# makey_makey.net
KiCad netlist of a schematic drawn in EAGLE
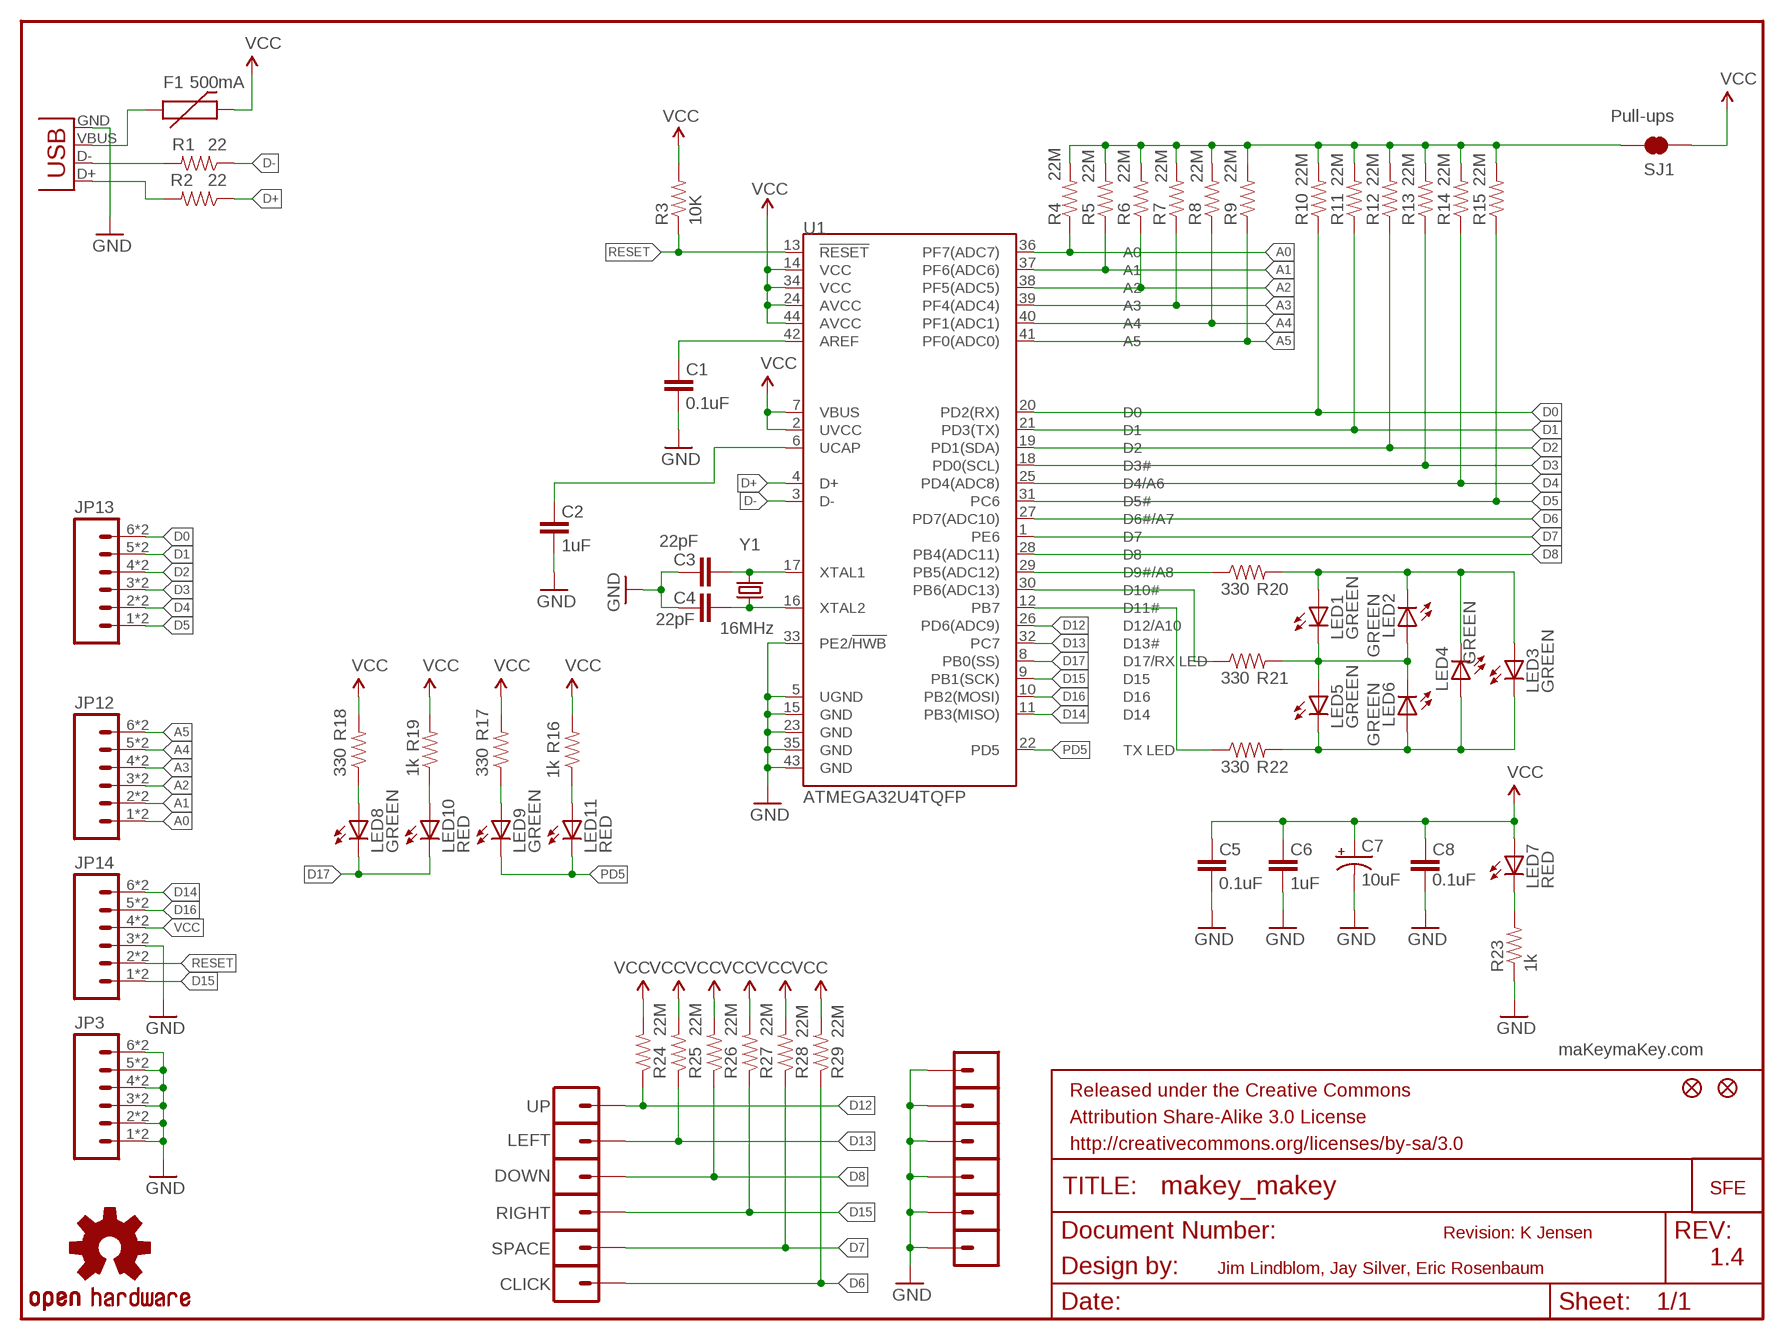
[diagram p0: schematic, sheet 1]

(export (version "E")
  (design (tool "Eeschema 10.0.6"))
  (components
    (comp (ref "C1")
      (value "0.1uF")
      (footprint "eagle-import:0603-CAP")
      (libsource (lib "eagle-import") (part "CAP0603-CAP"))
    )
    (comp (ref "C2")
      (value "1uF")
      (footprint "eagle-import:0603-CAP")
      (libsource (lib "eagle-import") (part "CAP0603-CAP"))
    )
    (comp (ref "C3")
      (value "22pF")
      (footprint "eagle-import:0603-CAP")
      (libsource (lib "eagle-import") (part "CAP0603-CAP"))
    )
    (comp (ref "C4")
      (value "22pF")
      (footprint "eagle-import:0603-CAP")
      (libsource (lib "eagle-import") (part "CAP0603-CAP"))
    )
    (comp (ref "C5")
      (value "0.1uF")
      (footprint "eagle-import:0603-CAP")
      (libsource (lib "eagle-import") (part "CAP0603-CAP"))
    )
    (comp (ref "C6")
      (value "1uF")
      (footprint "eagle-import:0603-CAP")
      (libsource (lib "eagle-import") (part "CAP0603-CAP"))
    )
    (comp (ref "C7")
      (value "10uF")
      (footprint "eagle-import:EIA3216")
      (libsource (lib "eagle-import") (part "CAP_POL1206"))
    )
    (comp (ref "C8")
      (value "0.1uF")
      (footprint "eagle-import:0603-CAP")
      (libsource (lib "eagle-import") (part "CAP0603-CAP"))
    )
    (comp (ref "CLICK")
      (value "M01ALLIGATOR-3MM")
      (footprint "eagle-import:1X01_ALLIGATOR_3MM")
      (libsource (lib "eagle-import") (part "M01ALLIGATOR-3MM"))
    )
    (comp (ref "DOWN")
      (value "M01ALLIGATOR-3MM")
      (footprint "eagle-import:1X01_ALLIGATOR_3MM")
      (libsource (lib "eagle-import") (part "M01ALLIGATOR-3MM"))
    )
    (comp (ref "F1")
      (value "500mA")
      (footprint "eagle-import:PTC-1206-WIDE")
      (libsource (lib "eagle-import") (part "PTCSMD-W"))
    )
    (comp (ref "JP1")
      (value "FIDUCIALUFIDUCIAL")
      (footprint "eagle-import:MICRO-FIDUCIAL")
      (libsource (lib "eagle-import") (part "FIDUCIALUFIDUCIAL"))
    )
    (comp (ref "JP2")
      (value "FIDUCIALUFIDUCIAL")
      (footprint "eagle-import:MICRO-FIDUCIAL")
      (libsource (lib "eagle-import") (part "FIDUCIALUFIDUCIAL"))
    )
    (comp (ref "JP3")
      (value "M06SMD-STRAIGHT-COMBO")
      (footprint "eagle-import:1X06_SMD_STRAIGHT_COMBO")
      (libsource (lib "eagle-import") (part "M06SMD-STRAIGHT-COMBO"))
    )
    (comp (ref "JP5")
      (value "M01ALLIGATOR-3MM")
      (footprint "eagle-import:1X01_ALLIGATOR_3MM")
      (libsource (lib "eagle-import") (part "M01ALLIGATOR-3MM"))
    )
    (comp (ref "JP6")
      (value "M01ALLIGATOR-3MM")
      (footprint "eagle-import:1X01_ALLIGATOR_3MM")
      (libsource (lib "eagle-import") (part "M01ALLIGATOR-3MM"))
    )
    (comp (ref "JP7")
      (value "M01ALLIGATOR-3MM")
      (footprint "eagle-import:1X01_ALLIGATOR_3MM")
      (libsource (lib "eagle-import") (part "M01ALLIGATOR-3MM"))
    )
    (comp (ref "JP8")
      (value "M01ALLIGATOR-3MM")
      (footprint "eagle-import:1X01_ALLIGATOR_3MM")
      (libsource (lib "eagle-import") (part "M01ALLIGATOR-3MM"))
    )
    (comp (ref "JP9")
      (value "LOGO-SFENEW")
      (footprint "eagle-import:SFE-NEW-WEBLOGO")
      (libsource (lib "eagle-import") (part "LOGO-SFENEW"))
    )
    (comp (ref "JP10")
      (value "M01ALLIGATOR-3MM")
      (footprint "eagle-import:1X01_ALLIGATOR_3MM")
      (libsource (lib "eagle-import") (part "M01ALLIGATOR-3MM"))
    )
    (comp (ref "JP11")
      (value "M01ALLIGATOR-3MM")
      (footprint "eagle-import:1X01_ALLIGATOR_3MM")
      (libsource (lib "eagle-import") (part "M01ALLIGATOR-3MM"))
    )
    (comp (ref "JP12")
      (value "M06SMD-STRAIGHT-COMBO")
      (footprint "eagle-import:1X06_SMD_STRAIGHT_COMBO")
      (libsource (lib "eagle-import") (part "M06SMD-STRAIGHT-COMBO"))
    )
    (comp (ref "JP13")
      (value "M06SMD-STRAIGHT-COMBO")
      (footprint "eagle-import:1X06_SMD_STRAIGHT_COMBO")
      (libsource (lib "eagle-import") (part "M06SMD-STRAIGHT-COMBO"))
    )
    (comp (ref "JP14")
      (value "M06SMD-STRAIGHT-COMBO")
      (footprint "eagle-import:1X06_SMD_STRAIGHT_COMBO")
      (libsource (lib "eagle-import") (part "M06SMD-STRAIGHT-COMBO"))
    )
    (comp (ref "LED1")
      (value "GREEN")
      (footprint "eagle-import:LED-1206-BOTTOM")
      (libsource (lib "eagle-import") (part "LED1206-BOTTOM"))
    )
    (comp (ref "LED2")
      (value "GREEN")
      (footprint "eagle-import:LED-1206-BOTTOM")
      (libsource (lib "eagle-import") (part "LED1206-BOTTOM"))
    )
    (comp (ref "LED3")
      (value "GREEN")
      (footprint "eagle-import:LED-1206-BOTTOM")
      (libsource (lib "eagle-import") (part "LED1206-BOTTOM"))
    )
    (comp (ref "LED4")
      (value "GREEN")
      (footprint "eagle-import:LED-1206-BOTTOM")
      (libsource (lib "eagle-import") (part "LED1206-BOTTOM"))
    )
    (comp (ref "LED5")
      (value "GREEN")
      (footprint "eagle-import:LED-1206-BOTTOM")
      (libsource (lib "eagle-import") (part "LED1206-BOTTOM"))
    )
    (comp (ref "LED6")
      (value "GREEN")
      (footprint "eagle-import:LED-1206-BOTTOM")
      (libsource (lib "eagle-import") (part "LED1206-BOTTOM"))
    )
    (comp (ref "LED7")
      (value "RED")
      (footprint "eagle-import:LED-0603")
      (libsource (lib "eagle-import") (part "LED0603"))
    )
    (comp (ref "LED8")
      (value "GREEN")
      (footprint "eagle-import:LED-0603")
      (libsource (lib "eagle-import") (part "SparkFun-LED_LED0603"))
    )
    (comp (ref "LED9")
      (value "GREEN")
      (footprint "eagle-import:LED-0603")
      (libsource (lib "eagle-import") (part "SparkFun-LED_LED0603"))
    )
    (comp (ref "LED10")
      (value "RED")
      (footprint "eagle-import:LED-0603")
      (libsource (lib "eagle-import") (part "SparkFun-LED_LED0603"))
    )
    (comp (ref "LED11")
      (value "RED")
      (footprint "eagle-import:LED-0603")
      (libsource (lib "eagle-import") (part "SparkFun-LED_LED0603"))
    )
    (comp (ref "LEFT")
      (value "M01ALLIGATOR-3MM")
      (footprint "eagle-import:1X01_ALLIGATOR_3MM")
      (libsource (lib "eagle-import") (part "M01ALLIGATOR-3MM"))
    )
    (comp (ref "R1")
      (value "22")
      (footprint "eagle-import:0603-RES")
      (libsource (lib "eagle-import") (part "RESISTOR0603-RES"))
    )
    (comp (ref "R2")
      (value "22")
      (footprint "eagle-import:0603-RES")
      (libsource (lib "eagle-import") (part "RESISTOR0603-RES"))
    )
    (comp (ref "R3")
      (value "10K")
      (footprint "eagle-import:0603-RES")
      (libsource (lib "eagle-import") (part "RESISTOR0603-RES"))
    )
    (comp (ref "R4")
      (value "22M")
      (footprint "eagle-import:0603-RES")
      (libsource (lib "eagle-import") (part "RESISTOR0603-RES"))
    )
    (comp (ref "R5")
      (value "22M")
      (footprint "eagle-import:0603-RES")
      (libsource (lib "eagle-import") (part "RESISTOR0603-RES"))
    )
    (comp (ref "R6")
      (value "22M")
      (footprint "eagle-import:0603-RES")
      (libsource (lib "eagle-import") (part "RESISTOR0603-RES"))
    )
    (comp (ref "R7")
      (value "22M")
      (footprint "eagle-import:0603-RES")
      (libsource (lib "eagle-import") (part "RESISTOR0603-RES"))
    )
    (comp (ref "R8")
      (value "22M")
      (footprint "eagle-import:0603-RES")
      (libsource (lib "eagle-import") (part "RESISTOR0603-RES"))
    )
    (comp (ref "R9")
      (value "22M")
      (footprint "eagle-import:0603-RES")
      (libsource (lib "eagle-import") (part "RESISTOR0603-RES"))
    )
    (comp (ref "R10")
      (value "22M")
      (footprint "eagle-import:0603-RES")
      (libsource (lib "eagle-import") (part "RESISTOR0603-RES"))
    )
    (comp (ref "R11")
      (value "22M")
      (footprint "eagle-import:0603-RES")
      (libsource (lib "eagle-import") (part "RESISTOR0603-RES"))
    )
    (comp (ref "R12")
      (value "22M")
      (footprint "eagle-import:0603-RES")
      (libsource (lib "eagle-import") (part "RESISTOR0603-RES"))
    )
    (comp (ref "R13")
      (value "22M")
      (footprint "eagle-import:0603-RES")
      (libsource (lib "eagle-import") (part "RESISTOR0603-RES"))
    )
    (comp (ref "R14")
      (value "22M")
      (footprint "eagle-import:0603-RES")
      (libsource (lib "eagle-import") (part "RESISTOR0603-RES"))
    )
    (comp (ref "R15")
      (value "22M")
      (footprint "eagle-import:0603-RES")
      (libsource (lib "eagle-import") (part "RESISTOR0603-RES"))
    )
    (comp (ref "R16")
      (value "1k")
      (footprint "eagle-import:0603-RES")
      (libsource (lib "eagle-import") (part "SparkFun-Passives_RESISTOR0603-RES"))
    )
    (comp (ref "R17")
      (value "330")
      (footprint "eagle-import:0603-RES")
      (libsource (lib "eagle-import") (part "SparkFun-Passives_RESISTOR0603-RES"))
    )
    (comp (ref "R18")
      (value "330")
      (footprint "eagle-import:0603-RES")
      (libsource (lib "eagle-import") (part "SparkFun-Passives_RESISTOR0603-RES"))
    )
    (comp (ref "R19")
      (value "1k")
      (footprint "eagle-import:0603-RES")
      (libsource (lib "eagle-import") (part "SparkFun-Passives_RESISTOR0603-RES"))
    )
    (comp (ref "R20")
      (value "330")
      (footprint "eagle-import:0603-RES")
      (libsource (lib "eagle-import") (part "SparkFun-Passives_RESISTOR0603-RES"))
    )
    (comp (ref "R21")
      (value "330")
      (footprint "eagle-import:0603-RES")
      (libsource (lib "eagle-import") (part "SparkFun-Passives_RESISTOR0603-RES"))
    )
    (comp (ref "R22")
      (value "330")
      (footprint "eagle-import:0603-RES")
      (libsource (lib "eagle-import") (part "SparkFun-Passives_RESISTOR0603-RES"))
    )
    (comp (ref "R23")
      (value "1k")
      (footprint "eagle-import:0603-RES")
      (libsource (lib "eagle-import") (part "RESISTOR0603-RES"))
    )
    (comp (ref "R24")
      (value "22M")
      (footprint "eagle-import:0603-RES")
      (libsource (lib "eagle-import") (part "RESISTOR0603-RES"))
    )
    (comp (ref "R25")
      (value "22M")
      (footprint "eagle-import:0603-RES")
      (libsource (lib "eagle-import") (part "RESISTOR0603-RES"))
    )
    (comp (ref "R26")
      (value "22M")
      (footprint "eagle-import:0603-RES")
      (libsource (lib "eagle-import") (part "RESISTOR0603-RES"))
    )
    (comp (ref "R27")
      (value "22M")
      (footprint "eagle-import:0603-RES")
      (libsource (lib "eagle-import") (part "RESISTOR0603-RES"))
    )
    (comp (ref "R28")
      (value "22M")
      (footprint "eagle-import:0603-RES")
      (libsource (lib "eagle-import") (part "RESISTOR0603-RES"))
    )
    (comp (ref "R29")
      (value "22M")
      (footprint "eagle-import:0603-RES")
      (libsource (lib "eagle-import") (part "RESISTOR0603-RES"))
    )
    (comp (ref "RIGHT")
      (value "M01ALLIGATOR-3MM")
      (footprint "eagle-import:1X01_ALLIGATOR_3MM")
      (libsource (lib "eagle-import") (part "M01ALLIGATOR-3MM"))
    )
    (comp (ref "SJ1")
      (value "Pull-ups")
      (footprint "eagle-import:SJ_2S-TRACE")
      (libsource (lib "eagle-import") (part "SOLDERJUMPER-OLDTRACE"))
    )
    (comp (ref "SPACE")
      (value "M01ALLIGATOR-3MM")
      (footprint "eagle-import:1X01_ALLIGATOR_3MM")
      (libsource (lib "eagle-import") (part "M01ALLIGATOR-3MM"))
    )
    (comp (ref "U$1")
      (value "OSHW-LOGOM")
      (footprint "eagle-import:OSHW-LOGO-M")
      (libsource (lib "eagle-import") (part "OSHW-LOGOM"))
    )
    (comp (ref "U1")
      (value "ATMEGA32U4TQFP")
      (footprint "eagle-import:TQFP44")
      (libsource (lib "eagle-import") (part "ATMEGA32U4TQFP"))
    )
    (comp (ref "UP")
      (value "M01ALLIGATOR-3MM")
      (footprint "eagle-import:1X01_ALLIGATOR_3MM")
      (libsource (lib "eagle-import") (part "M01ALLIGATOR-3MM"))
    )
    (comp (ref "X1")
      (value "USBSMD")
      (footprint "eagle-import:USB-MINIB")
      (libsource (lib "eagle-import") (part "USBSMD"))
    )
    (comp (ref "Y1")
      (value "16MHz")
      (footprint "eagle-import:CRYSTAL-SMD-5X3")
      (libsource (lib "eagle-import") (part "CRYSTAL5X3"))
    )
  )
  (nets
    (net (code "1") (name "A0") (class "Default")
      (node (ref "JP12") (pin "1") (pinfunction "1_1") (pintype "passive"))
      (node (ref "JP12") (pin "1-2") (pinfunction "1_1-2") (pintype "passive"))
      (node (ref "R4") (pin "1") (pinfunction "1_1") (pintype "passive"))
      (node (ref "U1") (pin "36") (pinfunction "PF7(ADC7)_36") (pintype "bidirectional"))
    )
    (net (code "2") (name "A1") (class "Default")
      (node (ref "JP12") (pin "2") (pinfunction "2_2") (pintype "passive"))
      (node (ref "JP12") (pin "2-2") (pinfunction "2_2-2") (pintype "passive"))
      (node (ref "R5") (pin "1") (pinfunction "1_1") (pintype "passive"))
      (node (ref "U1") (pin "37") (pinfunction "PF6(ADC6)_37") (pintype "bidirectional"))
    )
    (net (code "3") (name "A2") (class "Default")
      (node (ref "JP12") (pin "3") (pinfunction "3_3") (pintype "passive"))
      (node (ref "JP12") (pin "3-2") (pinfunction "3_3-2") (pintype "passive"))
      (node (ref "R6") (pin "1") (pinfunction "1_1") (pintype "passive"))
      (node (ref "U1") (pin "38") (pinfunction "PF5(ADC5)_38") (pintype "bidirectional"))
    )
    (net (code "4") (name "A3") (class "Default")
      (node (ref "JP12") (pin "4") (pinfunction "4_4") (pintype "passive"))
      (node (ref "JP12") (pin "4-2") (pinfunction "4_4-2") (pintype "passive"))
      (node (ref "R7") (pin "1") (pinfunction "1_1") (pintype "passive"))
      (node (ref "U1") (pin "39") (pinfunction "PF4(ADC4)_39") (pintype "bidirectional"))
    )
    (net (code "5") (name "A4") (class "Default")
      (node (ref "JP12") (pin "5") (pinfunction "5_5") (pintype "passive"))
      (node (ref "JP12") (pin "5-2") (pinfunction "5_5-2") (pintype "passive"))
      (node (ref "R8") (pin "1") (pinfunction "1_1") (pintype "passive"))
      (node (ref "U1") (pin "40") (pinfunction "PF1(ADC1)_40") (pintype "bidirectional"))
    )
    (net (code "6") (name "A5") (class "Default")
      (node (ref "JP12") (pin "6") (pinfunction "6_6") (pintype "passive"))
      (node (ref "JP12") (pin "6-2") (pinfunction "6_6-2") (pintype "passive"))
      (node (ref "R9") (pin "1") (pinfunction "1_1") (pintype "passive"))
      (node (ref "U1") (pin "41") (pinfunction "PF0(ADC0)_41") (pintype "bidirectional"))
    )
    (net (code "7") (name "D+") (class "Default")
      (node (ref "R2") (pin "1") (pinfunction "1_1") (pintype "passive"))
      (node (ref "U1") (pin "4") (pinfunction "D+_4") (pintype "bidirectional"))
    )
    (net (code "8") (name "D-") (class "Default")
      (node (ref "R1") (pin "1") (pinfunction "1_1") (pintype "passive"))
      (node (ref "U1") (pin "3") (pinfunction "D-_3") (pintype "bidirectional"))
    )
    (net (code "9") (name "D0") (class "Default")
      (node (ref "JP13") (pin "6") (pinfunction "6_6") (pintype "passive"))
      (node (ref "JP13") (pin "6-2") (pinfunction "6_6-2") (pintype "passive"))
      (node (ref "R10") (pin "1") (pinfunction "1_1") (pintype "passive"))
      (node (ref "U1") (pin "20") (pinfunction "PD2(RX)_20") (pintype "bidirectional"))
    )
    (net (code "10") (name "D1") (class "Default")
      (node (ref "JP13") (pin "5") (pinfunction "5_5") (pintype "passive"))
      (node (ref "JP13") (pin "5-2") (pinfunction "5_5-2") (pintype "passive"))
      (node (ref "R11") (pin "1") (pinfunction "1_1") (pintype "passive"))
      (node (ref "U1") (pin "21") (pinfunction "PD3(TX)_21") (pintype "bidirectional"))
    )
    (net (code "11") (name "D2") (class "Default")
      (node (ref "JP13") (pin "4") (pinfunction "4_4") (pintype "passive"))
      (node (ref "JP13") (pin "4-2") (pinfunction "4_4-2") (pintype "passive"))
      (node (ref "R12") (pin "1") (pinfunction "1_1") (pintype "passive"))
      (node (ref "U1") (pin "19") (pinfunction "PD1(SDA)_19") (pintype "bidirectional"))
    )
    (net (code "12") (name "D3") (class "Default")
      (node (ref "JP13") (pin "3") (pinfunction "3_3") (pintype "passive"))
      (node (ref "JP13") (pin "3-2") (pinfunction "3_3-2") (pintype "passive"))
      (node (ref "R13") (pin "1") (pinfunction "1_1") (pintype "passive"))
      (node (ref "U1") (pin "18") (pinfunction "PD0(SCL)_18") (pintype "bidirectional"))
    )
    (net (code "13") (name "D4") (class "Default")
      (node (ref "JP13") (pin "2") (pinfunction "2_2") (pintype "passive"))
      (node (ref "JP13") (pin "2-2") (pinfunction "2_2-2") (pintype "passive"))
      (node (ref "R14") (pin "1") (pinfunction "1_1") (pintype "passive"))
      (node (ref "U1") (pin "25") (pinfunction "PD4(ADC8)_25") (pintype "bidirectional"))
    )
    (net (code "14") (name "D5") (class "Default")
      (node (ref "JP13") (pin "1") (pinfunction "1_1") (pintype "passive"))
      (node (ref "JP13") (pin "1-2") (pinfunction "1_1-2") (pintype "passive"))
      (node (ref "R15") (pin "1") (pinfunction "1_1") (pintype "passive"))
      (node (ref "U1") (pin "31") (pinfunction "PC6_31") (pintype "bidirectional"))
    )
    (net (code "15") (name "D6") (class "Default")
      (node (ref "CLICK") (pin "1@0") (pinfunction "1_1@0") (pintype "passive"))
      (node (ref "CLICK") (pin "1@2") (pinfunction "1_1@2") (pintype "passive"))
      (node (ref "R29") (pin "1") (pinfunction "1_1") (pintype "passive"))
      (node (ref "U1") (pin "27") (pinfunction "PD7(ADC10)_27") (pintype "bidirectional"))
    )
    (net (code "16") (name "D7") (class "Default")
      (node (ref "R28") (pin "1") (pinfunction "1_1") (pintype "passive"))
      (node (ref "SPACE") (pin "1@0") (pinfunction "1_1@0") (pintype "passive"))
      (node (ref "SPACE") (pin "1@2") (pinfunction "1_1@2") (pintype "passive"))
      (node (ref "U1") (pin "1") (pinfunction "PE6_1") (pintype "bidirectional"))
    )
    (net (code "17") (name "D8") (class "Default")
      (node (ref "DOWN") (pin "1@0") (pinfunction "1_1@0") (pintype "passive"))
      (node (ref "DOWN") (pin "1@2") (pinfunction "1_1@2") (pintype "passive"))
      (node (ref "R26") (pin "1") (pinfunction "1_1") (pintype "passive"))
      (node (ref "U1") (pin "28") (pinfunction "PB4(ADC11)_28") (pintype "bidirectional"))
    )
    (net (code "18") (name "D12") (class "Default")
      (node (ref "R24") (pin "1") (pinfunction "1_1") (pintype "passive"))
      (node (ref "U1") (pin "26") (pinfunction "PD6(ADC9)_26") (pintype "bidirectional"))
      (node (ref "UP") (pin "1@0") (pinfunction "1_1@0") (pintype "passive"))
      (node (ref "UP") (pin "1@2") (pinfunction "1_1@2") (pintype "passive"))
    )
    (net (code "19") (name "D13") (class "Default")
      (node (ref "LEFT") (pin "1@0") (pinfunction "1_1@0") (pintype "passive"))
      (node (ref "LEFT") (pin "1@2") (pinfunction "1_1@2") (pintype "passive"))
      (node (ref "R25") (pin "1") (pinfunction "1_1") (pintype "passive"))
      (node (ref "U1") (pin "32") (pinfunction "PC7_32") (pintype "bidirectional"))
    )
    (net (code "20") (name "D14") (class "Default")
      (node (ref "JP14") (pin "6") (pinfunction "6_6") (pintype "passive"))
      (node (ref "JP14") (pin "6-2") (pinfunction "6_6-2") (pintype "passive"))
      (node (ref "U1") (pin "11") (pinfunction "PB3(MISO)_11") (pintype "bidirectional"))
    )
    (net (code "21") (name "D15") (class "Default")
      (node (ref "JP14") (pin "1") (pinfunction "1_1") (pintype "passive"))
      (node (ref "JP14") (pin "1-2") (pinfunction "1_1-2") (pintype "passive"))
      (node (ref "R27") (pin "1") (pinfunction "1_1") (pintype "passive"))
      (node (ref "RIGHT") (pin "1@0") (pinfunction "1_1@0") (pintype "passive"))
      (node (ref "RIGHT") (pin "1@2") (pinfunction "1_1@2") (pintype "passive"))
      (node (ref "U1") (pin "9") (pinfunction "PB1(SCK)_9") (pintype "bidirectional"))
    )
    (net (code "22") (name "D16") (class "Default")
      (node (ref "JP14") (pin "5") (pinfunction "5_5") (pintype "passive"))
      (node (ref "JP14") (pin "5-2") (pinfunction "5_5-2") (pintype "passive"))
      (node (ref "U1") (pin "10") (pinfunction "PB2(MOSI)_10") (pintype "bidirectional"))
    )
    (net (code "23") (name "D17") (class "Default")
      (node (ref "LED10") (pin "C") (pinfunction "C_C") (pintype "passive"))
      (node (ref "LED8") (pin "C") (pinfunction "C_C") (pintype "passive"))
      (node (ref "U1") (pin "8") (pinfunction "PB0(SS)_8") (pintype "bidirectional"))
    )
    (net (code "24") (name "GND") (class "Default")
      (node (ref "C1") (pin "1") (pinfunction "1_1") (pintype "passive"))
      (node (ref "C2") (pin "1") (pinfunction "1_1") (pintype "passive"))
      (node (ref "C3") (pin "2") (pinfunction "2_2") (pintype "passive"))
      (node (ref "C4") (pin "2") (pinfunction "2_2") (pintype "passive"))
      (node (ref "C5") (pin "1") (pinfunction "1_1") (pintype "passive"))
      (node (ref "C6") (pin "1") (pinfunction "1_1") (pintype "passive"))
      (node (ref "C7") (pin "C") (pinfunction "-_C") (pintype "passive"))
      (node (ref "C8") (pin "1") (pinfunction "1_1") (pintype "passive"))
      (node (ref "JP10") (pin "1@0") (pinfunction "1_1@0") (pintype "passive"))
      (node (ref "JP10") (pin "1@2") (pinfunction "1_1@2") (pintype "passive"))
      (node (ref "JP11") (pin "1@0") (pinfunction "1_1@0") (pintype "passive"))
      (node (ref "JP11") (pin "1@2") (pinfunction "1_1@2") (pintype "passive"))
      (node (ref "JP14") (pin "3") (pinfunction "3_3") (pintype "passive"))
      (node (ref "JP14") (pin "3-2") (pinfunction "3_3-2") (pintype "passive"))
      (node (ref "JP3") (pin "1") (pinfunction "1_1") (pintype "passive"))
      (node (ref "JP3") (pin "1-2") (pinfunction "1_1-2") (pintype "passive"))
      (node (ref "JP3") (pin "2") (pinfunction "2_2") (pintype "passive"))
      (node (ref "JP3") (pin "2-2") (pinfunction "2_2-2") (pintype "passive"))
      (node (ref "JP3") (pin "3") (pinfunction "3_3") (pintype "passive"))
      (node (ref "JP3") (pin "3-2") (pinfunction "3_3-2") (pintype "passive"))
      (node (ref "JP3") (pin "4") (pinfunction "4_4") (pintype "passive"))
      (node (ref "JP3") (pin "4-2") (pinfunction "4_4-2") (pintype "passive"))
      (node (ref "JP3") (pin "5") (pinfunction "5_5") (pintype "passive"))
      (node (ref "JP3") (pin "5-2") (pinfunction "5_5-2") (pintype "passive"))
      (node (ref "JP3") (pin "6") (pinfunction "6_6") (pintype "passive"))
      (node (ref "JP3") (pin "6-2") (pinfunction "6_6-2") (pintype "passive"))
      (node (ref "JP5") (pin "1@0") (pinfunction "1_1@0") (pintype "passive"))
      (node (ref "JP5") (pin "1@2") (pinfunction "1_1@2") (pintype "passive"))
      (node (ref "JP6") (pin "1@0") (pinfunction "1_1@0") (pintype "passive"))
      (node (ref "JP6") (pin "1@2") (pinfunction "1_1@2") (pintype "passive"))
      (node (ref "JP7") (pin "1@0") (pinfunction "1_1@0") (pintype "passive"))
      (node (ref "JP7") (pin "1@2") (pinfunction "1_1@2") (pintype "passive"))
      (node (ref "JP8") (pin "1@0") (pinfunction "1_1@0") (pintype "passive"))
      (node (ref "JP8") (pin "1@2") (pinfunction "1_1@2") (pintype "passive"))
      (node (ref "R23") (pin "1") (pinfunction "1_1") (pintype "passive"))
      (node (ref "U1") (pin "15") (pinfunction "GND_15") (pintype "bidirectional"))
      (node (ref "U1") (pin "23") (pinfunction "GND_23") (pintype "bidirectional"))
      (node (ref "U1") (pin "33") (pinfunction "PE2/~{HWB}_33") (pintype "bidirectional"))
      (node (ref "U1") (pin "35") (pinfunction "GND_35") (pintype "bidirectional"))
      (node (ref "U1") (pin "43") (pinfunction "GND_43") (pintype "bidirectional"))
      (node (ref "U1") (pin "5") (pinfunction "UGND_5") (pintype "bidirectional"))
      (node (ref "X1") (pin "GND") (pinfunction "GND_GND") (pintype "bidirectional"))
    )
    (net (code "25") (name "Net-(F1-Pad1)") (class "Default")
      (node (ref "F1") (pin "1") (pinfunction "1_1") (pintype "bidirectional"))
      (node (ref "X1") (pin "VBUS") (pinfunction "VBUS_VBUS") (pintype "bidirectional"))
    )
    (net (code "26") (name "Net-(LED1-PadA)") (class "Default")
      (node (ref "LED1") (pin "A") (pinfunction "A_A") (pintype "passive"))
      (node (ref "LED2") (pin "C") (pinfunction "C_C") (pintype "passive"))
      (node (ref "LED3") (pin "A") (pinfunction "A_A") (pintype "passive"))
      (node (ref "LED4") (pin "C") (pinfunction "C_C") (pintype "passive"))
      (node (ref "R20") (pin "2") (pinfunction "2_2") (pintype "passive"))
    )
    (net (code "27") (name "Net-(LED1-PadC)") (class "Default")
      (node (ref "LED1") (pin "C") (pinfunction "C_C") (pintype "passive"))
      (node (ref "LED2") (pin "A") (pinfunction "A_A") (pintype "passive"))
      (node (ref "LED5") (pin "A") (pinfunction "A_A") (pintype "passive"))
      (node (ref "LED6") (pin "C") (pinfunction "C_C") (pintype "passive"))
      (node (ref "R21") (pin "2") (pinfunction "2_2") (pintype "passive"))
    )
    (net (code "28") (name "Net-(LED3-PadC)") (class "Default")
      (node (ref "LED3") (pin "C") (pinfunction "C_C") (pintype "passive"))
      (node (ref "LED4") (pin "A") (pinfunction "A_A") (pintype "passive"))
      (node (ref "LED5") (pin "C") (pinfunction "C_C") (pintype "passive"))
      (node (ref "LED6") (pin "A") (pinfunction "A_A") (pintype "passive"))
      (node (ref "R22") (pin "2") (pinfunction "2_2") (pintype "passive"))
    )
    (net (code "29") (name "Net-(LED7-PadC)") (class "Default")
      (node (ref "LED7") (pin "C") (pinfunction "C_C") (pintype "passive"))
      (node (ref "R23") (pin "2") (pinfunction "2_2") (pintype "passive"))
    )
    (net (code "30") (name "Net-(LED8-PadA)") (class "Default")
      (node (ref "LED8") (pin "A") (pinfunction "A_A") (pintype "passive"))
      (node (ref "R18") (pin "1") (pinfunction "1_1") (pintype "passive"))
    )
    (net (code "31") (name "Net-(LED9-PadA)") (class "Default")
      (node (ref "LED9") (pin "A") (pinfunction "A_A") (pintype "passive"))
      (node (ref "R17") (pin "1") (pinfunction "1_1") (pintype "passive"))
    )
    (net (code "32") (name "Net-(LED10-PadA)") (class "Default")
      (node (ref "LED10") (pin "A") (pinfunction "A_A") (pintype "passive"))
      (node (ref "R19") (pin "1") (pinfunction "1_1") (pintype "passive"))
    )
    (net (code "33") (name "Net-(LED11-PadA)") (class "Default")
      (node (ref "LED11") (pin "A") (pinfunction "A_A") (pintype "passive"))
      (node (ref "R16") (pin "1") (pinfunction "1_1") (pintype "passive"))
    )
    (net (code "34") (name "Net-(R1-Pad2)") (class "Default")
      (node (ref "R1") (pin "2") (pinfunction "2_2") (pintype "passive"))
      (node (ref "X1") (pin "D-") (pinfunction "D-_D-") (pintype "bidirectional"))
    )
    (net (code "35") (name "Net-(R2-Pad2)") (class "Default")
      (node (ref "R2") (pin "2") (pinfunction "2_2") (pintype "passive"))
      (node (ref "X1") (pin "D+") (pinfunction "D+_D+") (pintype "bidirectional"))
    )
    (net (code "36") (name "Net-(R10-Pad2)") (class "Default")
      (node (ref "R10") (pin "2") (pinfunction "2_2") (pintype "passive"))
      (node (ref "R11") (pin "2") (pinfunction "2_2") (pintype "passive"))
      (node (ref "R12") (pin "2") (pinfunction "2_2") (pintype "passive"))
      (node (ref "R13") (pin "2") (pinfunction "2_2") (pintype "passive"))
      (node (ref "R14") (pin "2") (pinfunction "2_2") (pintype "passive"))
      (node (ref "R15") (pin "2") (pinfunction "2_2") (pintype "passive"))
      (node (ref "R4") (pin "2") (pinfunction "2_2") (pintype "passive"))
      (node (ref "R5") (pin "2") (pinfunction "2_2") (pintype "passive"))
      (node (ref "R6") (pin "2") (pinfunction "2_2") (pintype "passive"))
      (node (ref "R7") (pin "2") (pinfunction "2_2") (pintype "passive"))
      (node (ref "R8") (pin "2") (pinfunction "2_2") (pintype "passive"))
      (node (ref "R9") (pin "2") (pinfunction "2_2") (pintype "passive"))
      (node (ref "SJ1") (pin "2") (pinfunction "2_2") (pintype "passive"))
    )
    (net (code "37") (name "Net-(U1-AREF)") (class "Default")
      (node (ref "C1") (pin "2") (pinfunction "2_2") (pintype "passive"))
      (node (ref "U1") (pin "42") (pinfunction "AREF_42") (pintype "bidirectional"))
    )
    (net (code "38") (name "Net-(U1-PB5(ADC12))") (class "Default")
      (node (ref "R20") (pin "1") (pinfunction "1_1") (pintype "passive"))
      (node (ref "U1") (pin "29") (pinfunction "PB5(ADC12)_29") (pintype "bidirectional"))
    )
    (net (code "39") (name "Net-(U1-PB6(ADC13))") (class "Default")
      (node (ref "R21") (pin "1") (pinfunction "1_1") (pintype "passive"))
      (node (ref "U1") (pin "30") (pinfunction "PB6(ADC13)_30") (pintype "bidirectional"))
    )
    (net (code "40") (name "Net-(U1-PB7)") (class "Default")
      (node (ref "R22") (pin "1") (pinfunction "1_1") (pintype "passive"))
      (node (ref "U1") (pin "12") (pinfunction "PB7_12") (pintype "bidirectional"))
    )
    (net (code "41") (name "Net-(U1-UCAP)") (class "Default")
      (node (ref "C2") (pin "2") (pinfunction "2_2") (pintype "passive"))
      (node (ref "U1") (pin "6") (pinfunction "UCAP_6") (pintype "bidirectional"))
    )
    (net (code "42") (name "Net-(U1-XTAL1)") (class "Default")
      (node (ref "C3") (pin "1") (pinfunction "1_1") (pintype "passive"))
      (node (ref "U1") (pin "17") (pinfunction "XTAL1_17") (pintype "bidirectional"))
      (node (ref "Y1") (pin "3") (pinfunction "2_3") (pintype "passive"))
    )
    (net (code "43") (name "Net-(U1-XTAL2)") (class "Default")
      (node (ref "C4") (pin "1") (pinfunction "1_1") (pintype "passive"))
      (node (ref "U1") (pin "16") (pinfunction "XTAL2_16") (pintype "bidirectional"))
      (node (ref "Y1") (pin "1") (pinfunction "1_1") (pintype "passive"))
    )
    (net (code "44") (name "PD5") (class "Default")
      (node (ref "LED11") (pin "C") (pinfunction "C_C") (pintype "passive"))
      (node (ref "LED9") (pin "C") (pinfunction "C_C") (pintype "passive"))
      (node (ref "U1") (pin "22") (pinfunction "PD5_22") (pintype "bidirectional"))
    )
    (net (code "45") (name "RESET") (class "Default")
      (node (ref "JP14") (pin "2") (pinfunction "2_2") (pintype "passive"))
      (node (ref "JP14") (pin "2-2") (pinfunction "2_2-2") (pintype "passive"))
      (node (ref "R3") (pin "1") (pinfunction "1_1") (pintype "passive"))
      (node (ref "U1") (pin "13") (pinfunction "~{RESET}_13") (pintype "bidirectional"))
    )
    (net (code "46") (name "VCC") (class "Default")
      (node (ref "C5") (pin "2") (pinfunction "2_2") (pintype "passive"))
      (node (ref "C6") (pin "2") (pinfunction "2_2") (pintype "passive"))
      (node (ref "C7") (pin "A") (pinfunction "+_A") (pintype "passive"))
      (node (ref "C8") (pin "2") (pinfunction "2_2") (pintype "passive"))
      (node (ref "F1") (pin "2") (pinfunction "2_2") (pintype "bidirectional"))
      (node (ref "JP14") (pin "4") (pinfunction "4_4") (pintype "passive"))
      (node (ref "JP14") (pin "4-2") (pinfunction "4_4-2") (pintype "passive"))
      (node (ref "LED7") (pin "A") (pinfunction "A_A") (pintype "passive"))
      (node (ref "R16") (pin "2") (pinfunction "2_2") (pintype "passive"))
      (node (ref "R17") (pin "2") (pinfunction "2_2") (pintype "passive"))
      (node (ref "R18") (pin "2") (pinfunction "2_2") (pintype "passive"))
      (node (ref "R19") (pin "2") (pinfunction "2_2") (pintype "passive"))
      (node (ref "R24") (pin "2") (pinfunction "2_2") (pintype "passive"))
      (node (ref "R25") (pin "2") (pinfunction "2_2") (pintype "passive"))
      (node (ref "R26") (pin "2") (pinfunction "2_2") (pintype "passive"))
      (node (ref "R27") (pin "2") (pinfunction "2_2") (pintype "passive"))
      (node (ref "R28") (pin "2") (pinfunction "2_2") (pintype "passive"))
      (node (ref "R29") (pin "2") (pinfunction "2_2") (pintype "passive"))
      (node (ref "R3") (pin "2") (pinfunction "2_2") (pintype "passive"))
      (node (ref "SJ1") (pin "1") (pinfunction "1_1") (pintype "passive"))
      (node (ref "U1") (pin "14") (pinfunction "VCC_14") (pintype "bidirectional"))
      (node (ref "U1") (pin "2") (pinfunction "UVCC_2") (pintype "bidirectional"))
      (node (ref "U1") (pin "24") (pinfunction "AVCC_24") (pintype "bidirectional"))
      (node (ref "U1") (pin "34") (pinfunction "VCC_34") (pintype "bidirectional"))
      (node (ref "U1") (pin "44") (pinfunction "AVCC_44") (pintype "bidirectional"))
      (node (ref "U1") (pin "7") (pinfunction "VBUS_7") (pintype "bidirectional"))
    )
  )
)
